# dimmerPower.net
KiCad netlist of a schematic drawn in EAGLE
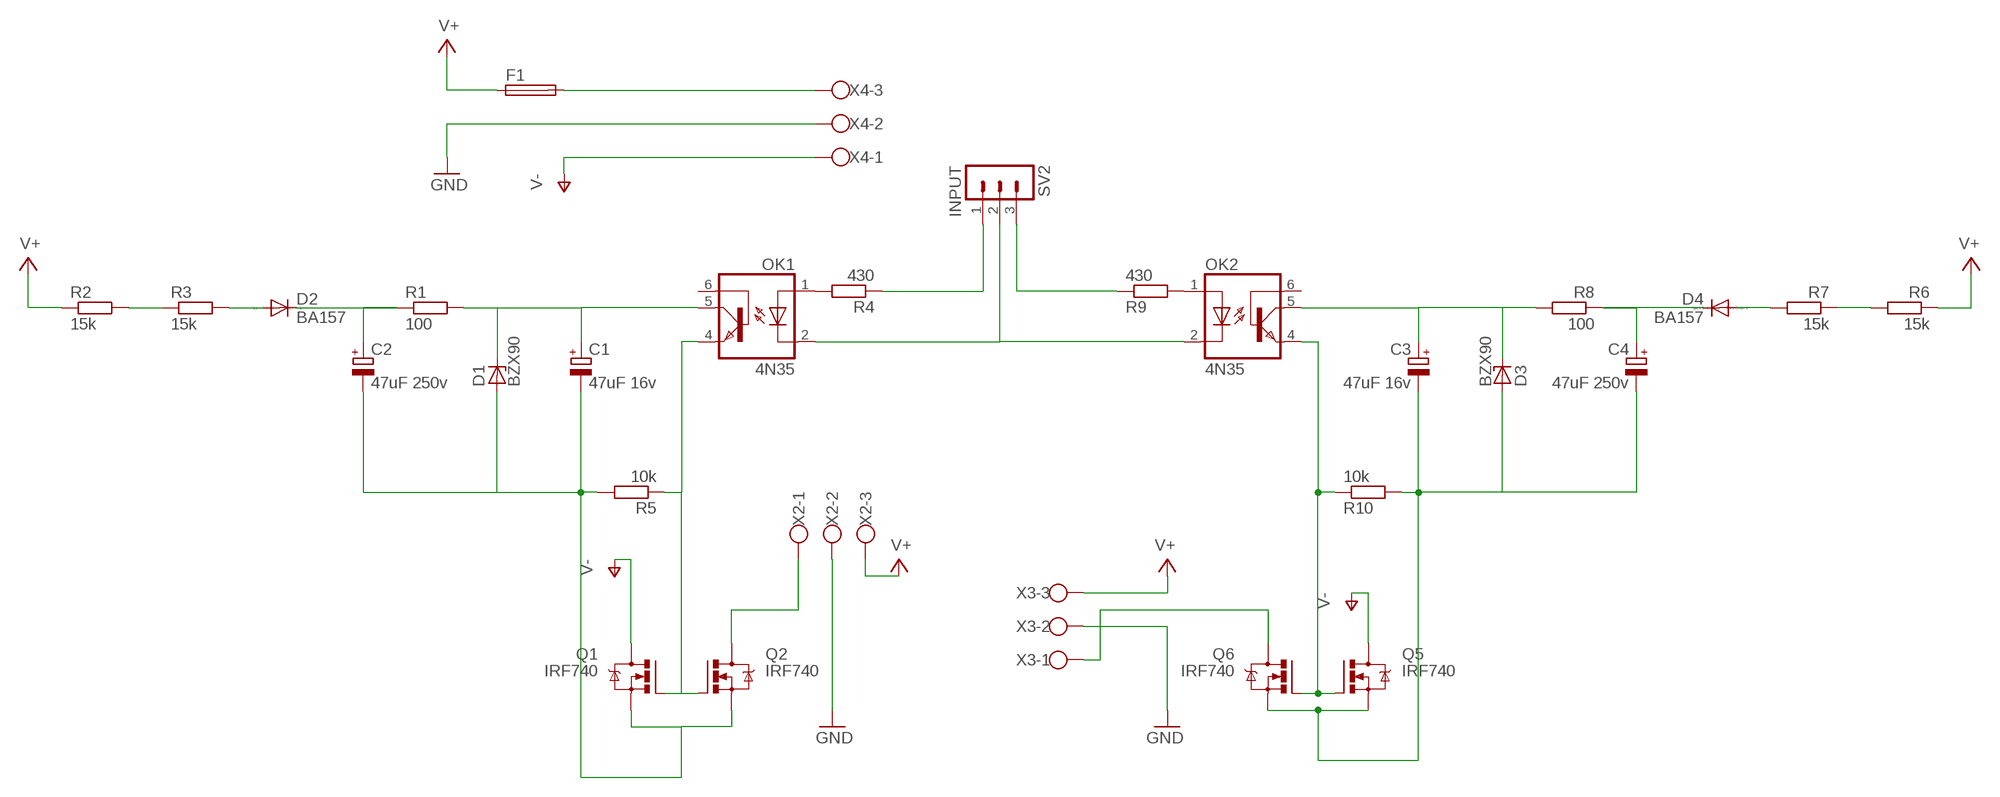
[diagram p0: schematic, sheet 1]

(export (version "E")
  (design (tool "Eeschema 10.0.6"))
  (components
    (comp (ref "C1")
      (value "47uF 16v")
      (footprint "eagle-import:E2,5-6")
      (libsource (lib "eagle-import") (part "CPOL-EUE2.5-6"))
    )
    (comp (ref "C2")
      (value "47uF 250v")
      (footprint "eagle-import:E5-13")
      (libsource (lib "eagle-import") (part "CPOL-EUE5-13"))
    )
    (comp (ref "C3")
      (value "47uF 16v")
      (footprint "eagle-import:E2,5-6")
      (libsource (lib "eagle-import") (part "CPOL-EUE2.5-6"))
    )
    (comp (ref "C4")
      (value "47uF 250v")
      (footprint "eagle-import:E5-13")
      (libsource (lib "eagle-import") (part "CPOL-EUE5-13"))
    )
    (comp (ref "D1")
      (value "BZX90")
      (footprint "eagle-import:DO34Z7")
      (libsource (lib "eagle-import") (part "BZX90"))
    )
    (comp (ref "D2")
      (value "BA157")
      (footprint "eagle-import:P1-10")
      (libsource (lib "eagle-import") (part "BA157"))
    )
    (comp (ref "D3")
      (value "BZX90")
      (footprint "eagle-import:DO34Z7")
      (libsource (lib "eagle-import") (part "BZX90"))
    )
    (comp (ref "D4")
      (value "BA157")
      (footprint "eagle-import:P1-10")
      (libsource (lib "eagle-import") (part "BA157"))
    )
    (comp (ref "F1")
      (value "SH22,5")
      (footprint "eagle-import:SH22,5")
      (fields (field (name "MF") "SCHURTER") (field (name "MPN") "0031.8201"))
      (libsource (lib "eagle-import") (part "SH22,5"))
    )
    (comp (ref "OK1")
      (value "4N35")
      (footprint "eagle-import:DIL06")
      (fields (field (name "MF") "FAIRCHILD SEMICONDUCTOR"))
      (libsource (lib "eagle-import") (part "4N35"))
    )
    (comp (ref "OK2")
      (value "4N35")
      (footprint "eagle-import:DIL06")
      (fields (field (name "MF") "FAIRCHILD SEMICONDUCTOR"))
      (libsource (lib "eagle-import") (part "4N35"))
    )
    (comp (ref "Q1")
      (value "IRF740")
      (footprint "eagle-import:TO220BV")
      (libsource (lib "eagle-import") (part "IRF740"))
    )
    (comp (ref "Q2")
      (value "IRF740")
      (footprint "eagle-import:TO220BV")
      (libsource (lib "eagle-import") (part "IRF740"))
    )
    (comp (ref "Q5")
      (value "IRF740")
      (footprint "eagle-import:TO220BV")
      (libsource (lib "eagle-import") (part "IRF740"))
    )
    (comp (ref "Q6")
      (value "IRF740")
      (footprint "eagle-import:TO220BV")
      (libsource (lib "eagle-import") (part "IRF740"))
    )
    (comp (ref "R1")
      (value "100")
      (footprint "eagle-import:0204_7")
      (libsource (lib "eagle-import") (part "R-EU_0204/7"))
    )
    (comp (ref "R2")
      (value "15k")
      (footprint "eagle-import:P0613_15")
      (libsource (lib "eagle-import") (part "R-EU_0613/15"))
    )
    (comp (ref "R3")
      (value "15k")
      (footprint "eagle-import:P0613_15")
      (libsource (lib "eagle-import") (part "R-EU_0613/15"))
    )
    (comp (ref "R4")
      (value "430")
      (footprint "eagle-import:0204_7")
      (libsource (lib "eagle-import") (part "R-EU_0204/7"))
    )
    (comp (ref "R5")
      (value "10k")
      (footprint "eagle-import:0204_7")
      (libsource (lib "eagle-import") (part "R-EU_0204/7"))
    )
    (comp (ref "R6")
      (value "15k")
      (footprint "eagle-import:P0613_15")
      (libsource (lib "eagle-import") (part "R-EU_0613/15"))
    )
    (comp (ref "R7")
      (value "15k")
      (footprint "eagle-import:P0613_15")
      (libsource (lib "eagle-import") (part "R-EU_0613/15"))
    )
    (comp (ref "R8")
      (value "100")
      (footprint "eagle-import:0204_7")
      (libsource (lib "eagle-import") (part "R-EU_0204/7"))
    )
    (comp (ref "R9")
      (value "430")
      (footprint "eagle-import:0204_7")
      (libsource (lib "eagle-import") (part "R-EU_0204/7"))
    )
    (comp (ref "R10")
      (value "10k")
      (footprint "eagle-import:0204_7")
      (libsource (lib "eagle-import") (part "R-EU_0204/7"))
    )
    (comp (ref "SV2")
      (value "INPUT")
      (footprint "eagle-import:MA03-1")
      (libsource (lib "eagle-import") (part "MA03-1"))
    )
    (comp (ref "X2")
      (value "W237-103")
      (footprint "eagle-import:W237-103")
      (fields (field (name "MPN") "237-103"))
      (libsource (lib "eagle-import") (part "W237-103"))
    )
    (comp (ref "X3")
      (value "W237-103")
      (footprint "eagle-import:W237-103")
      (fields (field (name "MPN") "237-103"))
      (libsource (lib "eagle-import") (part "W237-103"))
    )
    (comp (ref "X4")
      (value "W237-103")
      (footprint "eagle-import:W237-103")
      (fields (field (name "MPN") "237-103"))
      (libsource (lib "eagle-import") (part "W237-103"))
    )
  )
  (nets
    (net (code "1") (name "GND") (class "Default")
      (node (ref "X2") (pin "2") (pinfunction "KL_2") (pintype "passive"))
      (node (ref "X3") (pin "2") (pinfunction "KL_2") (pintype "passive"))
      (node (ref "X4") (pin "2") (pinfunction "KL_2") (pintype "passive"))
    )
    (net (code "2") (name "Net-(C1-Pad-)") (class "Default")
      (node (ref "C1") (pin "-") (pinfunction "-_-") (pintype "passive"))
      (node (ref "C2") (pin "-") (pinfunction "-_-") (pintype "passive"))
      (node (ref "D1") (pin "A") (pinfunction "A_A") (pintype "passive"))
      (node (ref "Q1") (pin "S") (pinfunction "S_S") (pintype "passive"))
      (node (ref "Q2") (pin "S") (pinfunction "S_S") (pintype "passive"))
      (node (ref "R5") (pin "2") (pinfunction "2_2") (pintype "passive"))
    )
    (net (code "3") (name "Net-(C2-Pad+)") (class "Default")
      (node (ref "C2") (pin "+") (pinfunction "+_+") (pintype "passive"))
      (node (ref "D2") (pin "C") (pinfunction "C_C") (pintype "passive"))
      (node (ref "R1") (pin "1") (pinfunction "1_1") (pintype "passive"))
    )
    (net (code "4") (name "Net-(C3-Pad-)") (class "Default")
      (node (ref "C3") (pin "-") (pinfunction "-_-") (pintype "passive"))
      (node (ref "C4") (pin "-") (pinfunction "-_-") (pintype "passive"))
      (node (ref "D3") (pin "A") (pinfunction "A_A") (pintype "passive"))
      (node (ref "Q5") (pin "S") (pinfunction "S_S") (pintype "passive"))
      (node (ref "Q6") (pin "S") (pinfunction "S_S") (pintype "passive"))
      (node (ref "R10") (pin "2") (pinfunction "2_2") (pintype "passive"))
    )
    (net (code "5") (name "Net-(C4-Pad+)") (class "Default")
      (node (ref "C4") (pin "+") (pinfunction "+_+") (pintype "passive"))
      (node (ref "D4") (pin "C") (pinfunction "C_C") (pintype "passive"))
      (node (ref "R8") (pin "1") (pinfunction "1_1") (pintype "passive"))
    )
    (net (code "6") (name "Net-(D2-PadA)") (class "Default")
      (node (ref "D2") (pin "A") (pinfunction "A_A") (pintype "passive"))
      (node (ref "R3") (pin "2") (pinfunction "2_2") (pintype "passive"))
    )
    (net (code "7") (name "Net-(D4-PadA)") (class "Default")
      (node (ref "D4") (pin "A") (pinfunction "A_A") (pintype "passive"))
      (node (ref "R7") (pin "2") (pinfunction "2_2") (pintype "passive"))
    )
    (net (code "8") (name "Net-(OK1-A)") (class "Default")
      (node (ref "OK1") (pin "1") (pinfunction "A_1") (pintype "passive"))
      (node (ref "R4") (pin "2") (pinfunction "2_2") (pintype "passive"))
    )
    (net (code "9") (name "Net-(OK1-C)") (class "Default")
      (node (ref "OK1") (pin "2") (pinfunction "C_2") (pintype "passive"))
      (node (ref "OK2") (pin "2") (pinfunction "C_2") (pintype "passive"))
      (node (ref "SV2") (pin "2") (pinfunction "2_2") (pintype "passive"))
    )
    (net (code "10") (name "Net-(OK1-COL)") (class "Default")
      (node (ref "C1") (pin "+") (pinfunction "+_+") (pintype "passive"))
      (node (ref "D1") (pin "C") (pinfunction "C_C") (pintype "passive"))
      (node (ref "OK1") (pin "5") (pinfunction "COL_5") (pintype "passive"))
      (node (ref "R1") (pin "2") (pinfunction "2_2") (pintype "passive"))
    )
    (net (code "11") (name "Net-(OK1-EMI)") (class "Default")
      (node (ref "OK1") (pin "4") (pinfunction "EMI_4") (pintype "passive"))
      (node (ref "Q1") (pin "G") (pinfunction "G_G") (pintype "passive"))
      (node (ref "Q2") (pin "G") (pinfunction "G_G") (pintype "passive"))
      (node (ref "R5") (pin "1") (pinfunction "1_1") (pintype "passive"))
    )
    (net (code "12") (name "Net-(OK2-A)") (class "Default")
      (node (ref "OK2") (pin "1") (pinfunction "A_1") (pintype "passive"))
      (node (ref "R9") (pin "2") (pinfunction "2_2") (pintype "passive"))
    )
    (net (code "13") (name "Net-(OK2-COL)") (class "Default")
      (node (ref "C3") (pin "+") (pinfunction "+_+") (pintype "passive"))
      (node (ref "D3") (pin "C") (pinfunction "C_C") (pintype "passive"))
      (node (ref "OK2") (pin "5") (pinfunction "COL_5") (pintype "passive"))
      (node (ref "R8") (pin "2") (pinfunction "2_2") (pintype "passive"))
    )
    (net (code "14") (name "Net-(OK2-EMI)") (class "Default")
      (node (ref "OK2") (pin "4") (pinfunction "EMI_4") (pintype "passive"))
      (node (ref "Q5") (pin "G") (pinfunction "G_G") (pintype "passive"))
      (node (ref "Q6") (pin "G") (pinfunction "G_G") (pintype "passive"))
      (node (ref "R10") (pin "1") (pinfunction "1_1") (pintype "passive"))
    )
    (net (code "15") (name "Net-(R2-Pad2)") (class "Default")
      (node (ref "R2") (pin "2") (pinfunction "2_2") (pintype "passive"))
      (node (ref "R3") (pin "1") (pinfunction "1_1") (pintype "passive"))
    )
    (net (code "16") (name "Net-(R4-Pad1)") (class "Default")
      (node (ref "R4") (pin "1") (pinfunction "1_1") (pintype "passive"))
      (node (ref "SV2") (pin "1") (pinfunction "1_1") (pintype "passive"))
    )
    (net (code "17") (name "Net-(R6-Pad2)") (class "Default")
      (node (ref "R6") (pin "2") (pinfunction "2_2") (pintype "passive"))
      (node (ref "R7") (pin "1") (pinfunction "1_1") (pintype "passive"))
    )
    (net (code "18") (name "Net-(R9-Pad1)") (class "Default")
      (node (ref "R9") (pin "1") (pinfunction "1_1") (pintype "passive"))
      (node (ref "SV2") (pin "3") (pinfunction "3_3") (pintype "passive"))
    )
    (net (code "19") (name "Net-(X2A-KL)") (class "Default")
      (node (ref "Q2") (pin "D") (pinfunction "D_D") (pintype "passive"))
      (node (ref "X2") (pin "1") (pinfunction "KL_1") (pintype "passive"))
    )
    (net (code "20") (name "Net-(X3A-KL)") (class "Default")
      (node (ref "Q6") (pin "D") (pinfunction "D_D") (pintype "passive"))
      (node (ref "X3") (pin "1") (pinfunction "KL_1") (pintype "passive"))
    )
    (net (code "21") (name "Net-(X4C-KL)") (class "Default")
      (node (ref "F1") (pin "2") (pinfunction "2_2") (pintype "passive"))
      (node (ref "X4") (pin "3") (pinfunction "KL_3") (pintype "passive"))
    )
    (net (code "22") (name "V+") (class "Default")
      (node (ref "F1") (pin "1") (pinfunction "1_1") (pintype "passive"))
      (node (ref "R2") (pin "1") (pinfunction "1_1") (pintype "passive"))
      (node (ref "R6") (pin "1") (pinfunction "1_1") (pintype "passive"))
      (node (ref "X2") (pin "3") (pinfunction "KL_3") (pintype "passive"))
      (node (ref "X3") (pin "3") (pinfunction "KL_3") (pintype "passive"))
    )
    (net (code "23") (name "V-") (class "Default")
      (node (ref "Q1") (pin "D") (pinfunction "D_D") (pintype "passive"))
      (node (ref "Q5") (pin "D") (pinfunction "D_D") (pintype "passive"))
      (node (ref "X4") (pin "1") (pinfunction "KL_1") (pintype "passive"))
    )
    (net (code "24") (name "unconnected-(OK1-BAS-Pad6)") (class "Default")
      (node (ref "OK1") (pin "6") (pinfunction "BAS_6") (pintype "passive"))
    )
    (net (code "25") (name "unconnected-(OK2-BAS-Pad6)") (class "Default")
      (node (ref "OK2") (pin "6") (pinfunction "BAS_6") (pintype "passive"))
    )
  )
)
